# jetson_agx_m_2.net
KiCad netlist of a schematic drawn in Altium Designer
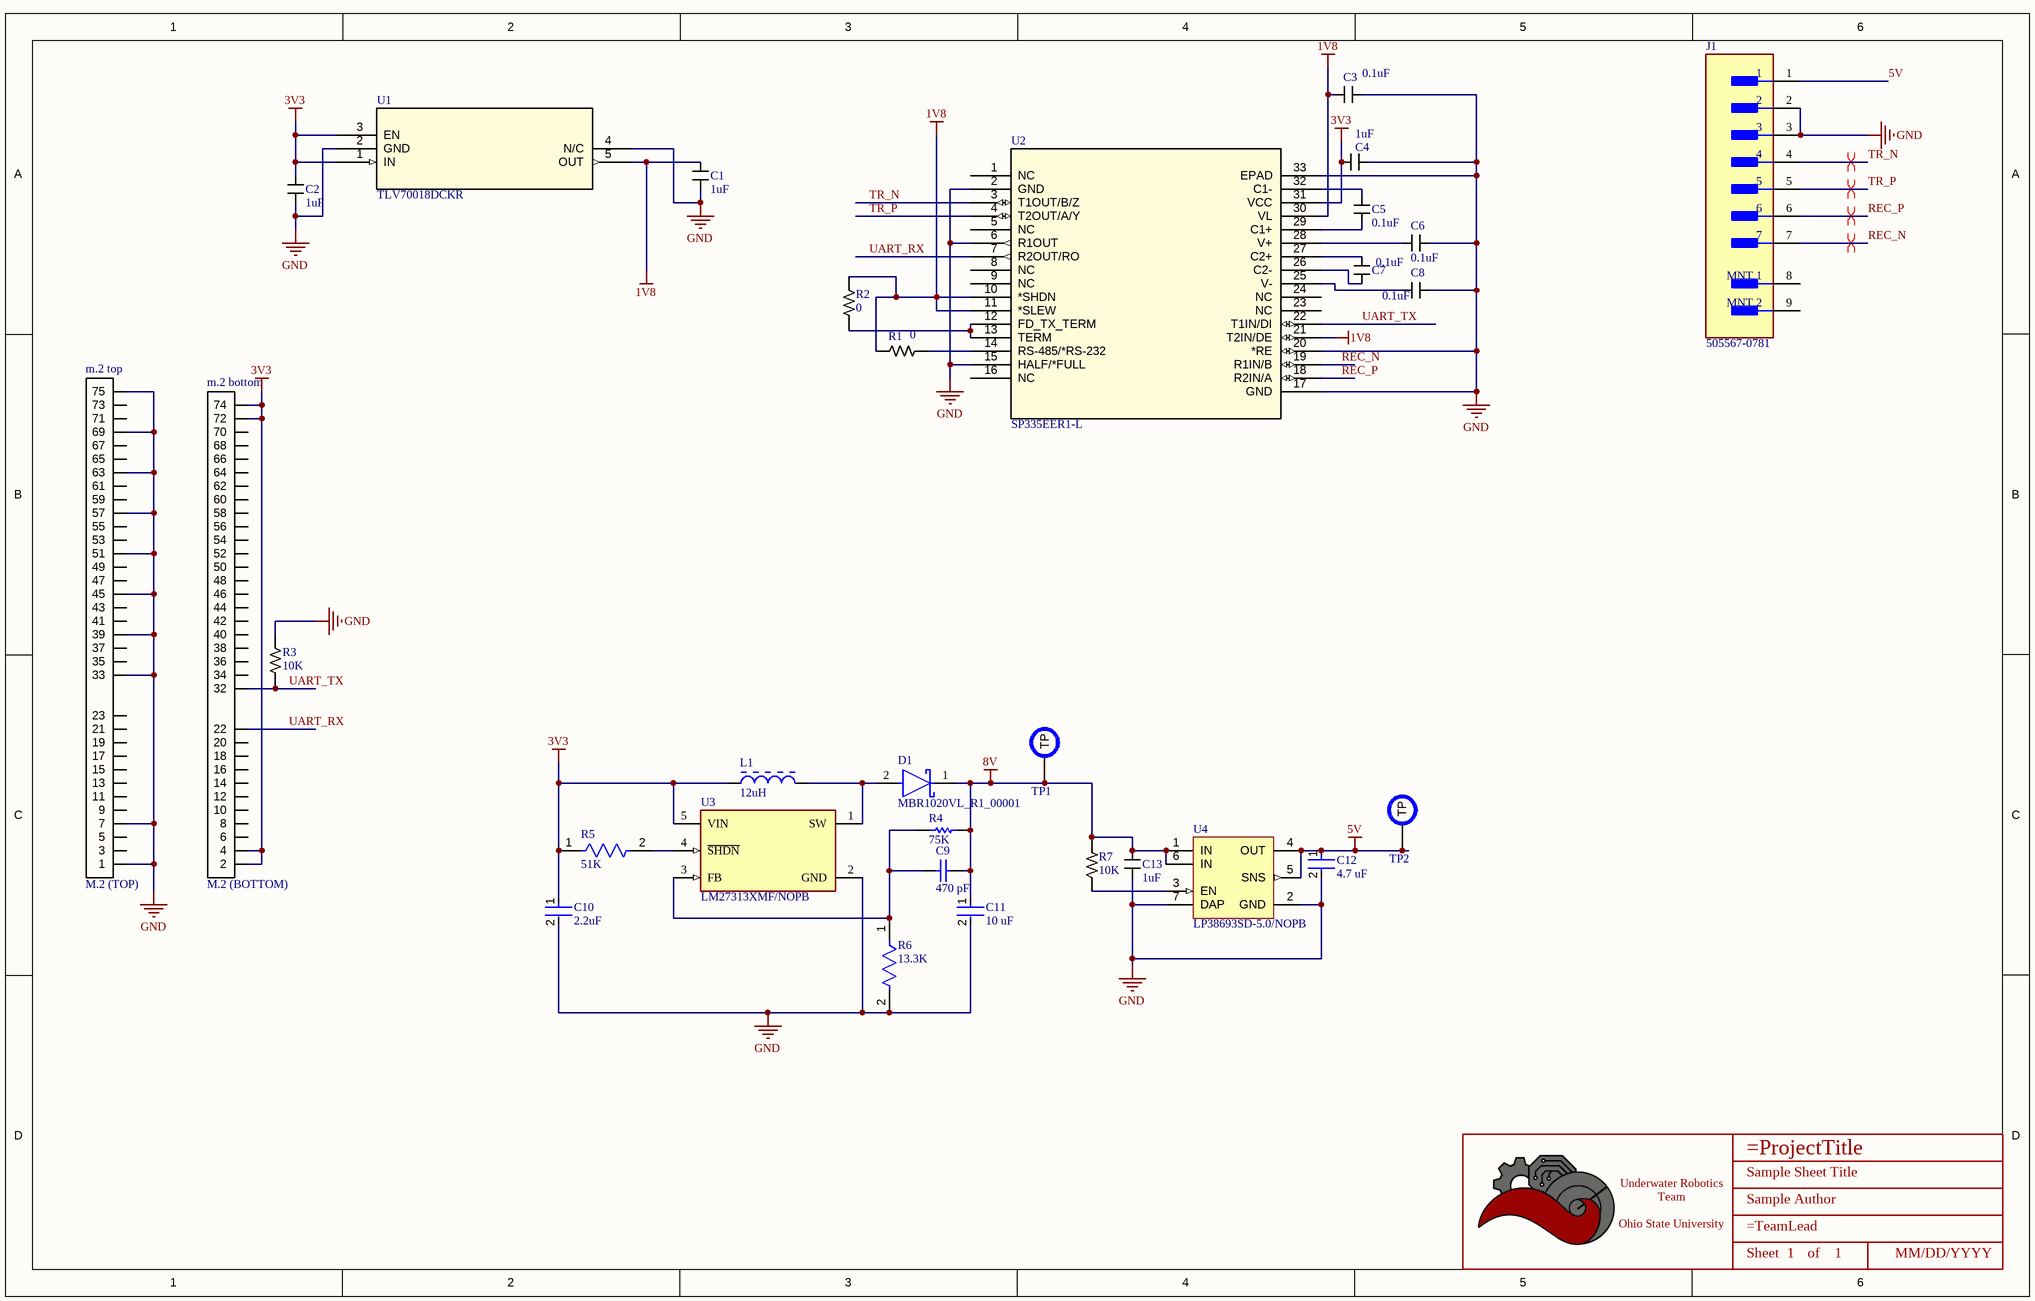
[diagram p0: jetson_agx_m.2.SchDoc]

(export (version "E")
  (design (tool "Eeschema 10.0.6"))
  (components
    (comp (ref "*")
      (value "Title_Block")
      (footprint "LOGO")
      (description "UWRT Schematic Title Block Template\r\n\r\nCreated June 2021, Dylan Trainor")
      (libsource (lib "UWRT") (part "Title_Block"))
    )
    (comp (ref "C1")
      (value "1uF")
      (footprint "CAPACITOR_0402")
      (description "Cap 1uF 16V +/-10%\r\nCeramic 0402")
      (fields
        (field (name "TOLERANCE") "+/- 10%")
        (field (name "VOLTAGE") "16V")
        (field (name "MADE BY") "Robert Pafford")
      )
      (libsource (lib "Capacitors") (part "CAPACITOR_1uF_0402"))
    )
    (comp (ref "C2")
      (value "1uF")
      (footprint "CAPACITOR_0402")
      (description "Cap 1uF 16V +/-10%\r\nCeramic 0402")
      (fields
        (field (name "TOLERANCE") "+/- 10%")
        (field (name "VOLTAGE") "16V")
        (field (name "MADE BY") "Robert Pafford")
      )
      (libsource (lib "Capacitors") (part "CAPACITOR_1uF_0402"))
    )
    (comp (ref "C3")
      (value "0.1uF")
      (footprint "CAPACITOR_0402")
      (description "Cap 100nF 25V +/-10%\r\nCeramic 0402")
      (fields
        (field (name "TOLERANCE") "+/- 10%")
        (field (name "VOLTAGE") "25V")
        (field (name "MADE BY") "Robert Pafford")
      )
      (libsource (lib "Capacitors") (part "CAPACITOR_0.1uF_0402"))
    )
    (comp (ref "C4")
      (value "1uF")
      (footprint "CAPACITOR_0402")
      (description "Cap 1uF 16V +/-10%\r\nCeramic 0402")
      (fields
        (field (name "TOLERANCE") "+/- 10%")
        (field (name "VOLTAGE") "16V")
        (field (name "MADE BY") "Robert Pafford")
      )
      (libsource (lib "Capacitors") (part "CAPACITOR_1uF_0402"))
    )
    (comp (ref "C5")
      (value "0.1uF")
      (footprint "CAPACITOR_0402")
      (description "Cap 100nF 25V +/-10%\r\nCeramic 0402")
      (fields
        (field (name "TOLERANCE") "+/- 10%")
        (field (name "VOLTAGE") "25V")
        (field (name "MADE BY") "Robert Pafford")
      )
      (libsource (lib "Capacitors") (part "CAPACITOR_0.1uF_0402"))
    )
    (comp (ref "C6")
      (value "0.1uF")
      (footprint "CAPACITOR_0402")
      (description "Cap 100nF 25V +/-10%\r\nCeramic 0402")
      (fields
        (field (name "TOLERANCE") "+/- 10%")
        (field (name "VOLTAGE") "25V")
        (field (name "MADE BY") "Robert Pafford")
      )
      (libsource (lib "Capacitors") (part "CAPACITOR_0.1uF_0402"))
    )
    (comp (ref "C7")
      (value "0.1uF")
      (footprint "CAPACITOR_0402")
      (description "Cap 100nF 25V +/-10%\r\nCeramic 0402")
      (fields
        (field (name "TOLERANCE") "+/- 10%")
        (field (name "VOLTAGE") "25V")
        (field (name "MADE BY") "Robert Pafford")
      )
      (libsource (lib "Capacitors") (part "CAPACITOR_0.1uF_0402"))
    )
    (comp (ref "C8")
      (value "0.1uF")
      (footprint "CAPACITOR_0402")
      (description "Cap 100nF 25V +/-10%\r\nCeramic 0402")
      (fields
        (field (name "TOLERANCE") "+/- 10%")
        (field (name "VOLTAGE") "25V")
        (field (name "MADE BY") "Robert Pafford")
      )
      (libsource (lib "Capacitors") (part "CAPACITOR_0.1uF_0402"))
    )
    (comp (ref "C9")
      (value "470 pF")
      (footprint "CAPC1005X55X25LL05T05")
      (fields (field (name "PART NUMBER") "VJ0402Y471KXQCW1BC") (field (name "MANUFACTURER") "Vitramon"))
      (libsource (lib "Altium Content Vault") (part "CAP"))
    )
    (comp (ref "C10")
      (value "2.2uF")
      (footprint "FP-GRT155-0_2-IPC_C")
      (description "Multi-Layer Ceramic Capacitor 2.2uF 10V X6S ±10% 0402 Paper T/R")
      (fields (field (name "TOLERANCE") "10%"))
      (libsource (lib "Altium Content Vault") (part "02cd4be3c70576c341d710602a673aa"))
    )
    (comp (ref "C11")
      (value "10 uF")
      (footprint "FP-CL07-IPC_C")
      (description "Cap Ceramic 10uF 10V X5R ±20% SMD 0402 +85°C Paper T/R")
      (fields (field (name "TOLERANCE") "20%"))
      (libsource (lib "Altium Content Vault") (part "b4654b650e69147ec39a6b967a45e02"))
    )
    (comp (ref "C12")
      (value "4.7 uF")
      (footprint "FP-CL282-IPC_C")
      (description "Cap Ceramic 4.7uF 10V X5R ±20% SMD 0402 +85°C Paper T/R")
      (fields (field (name "TOLERANCE") "20%"))
      (libsource (lib "Altium Content Vault") (part "b4654b650e69147ec39a6b967a45e02"))
    )
    (comp (ref "C13")
      (value "1uF")
      (footprint "CAPACITOR_0402")
      (description "Cap 1uF 16V +/-10%\r\nCeramic 0402")
      (fields
        (field (name "TOLERANCE") "+/- 10%")
        (field (name "VOLTAGE") "16V")
        (field (name "MADE BY") "Robert Pafford")
      )
      (libsource (lib "Capacitors") (part "CAPACITOR_1uF_0402"))
    )
    (comp (ref "D1")
      (value "MBR1020VL_R1_00001")
      (footprint "FP-MBR1020VL_R1_00001-MFG")
      (description "DIODE SCHOTTKY 20V 1A SOD123FL")
      (libsource (lib "Altium Content Vault") (part "c1678fac7984e62e0809fbf79c06691"))
    )
    (comp (ref "J1")
      (value "505567-0781")
      (footprint "FP-505567-0781-MFG")
      (libsource (lib "Altium Content Vault") (part "b0abd15a4b949e48c0a2e6945bb7dcd"))
    )
    (comp (ref "L1")
      (value "12uH")
      (footprint "BOUR-SDR0403-2_V")
      (fields (field (name "PARTNUMBER") "SDR0403-120ML") (field (name "MANUFACTURER") "Bourns"))
      (libsource (lib "Altium Content Vault") (part "BOUR-IND-2A"))
    )
    (comp (ref "m.2 bottom")
      (value "M.2 (BOTTOM)")
      (footprint "M.2 (bottom)")
      (fields (field (name "CREATED BY") "Ethan Rosati") (field (name "REVIEWED BY") "*"))
      (libsource (lib "Connectors") (part "M.2 (BOTTOM)"))
    )
    (comp (ref "m.2 top")
      (value "M.2 (TOP)")
      (footprint "M.2 (top)")
      (description "M.2 E-Key top fingers")
      (fields (field (name "CREATED BY") "Ethan Rosati") (field (name "REVIEWED BY") "*"))
      (libsource (lib "Connectors") (part "M.2 (TOP)"))
    )
    (comp (ref "R1")
      (value "0 Ohm 1% 1/16W")
      (footprint "RESISTOR_0402")
      (description "RES 0 OHM 1% 1/16W 0402")
      (fields
        (field (name "TOLERANCE") "+/- 1%")
        (field (name "VALUE  (OHMS)") "0")
        (field (name "MADE BY") "Robert Pafford")
      )
      (libsource (lib "Resistors") (part "RESISTOR_0_0402"))
    )
    (comp (ref "R2")
      (value "0 Ohm 1% 1/16W")
      (footprint "RESISTOR_0402")
      (description "RES 0 OHM 1% 1/16W 0402")
      (fields
        (field (name "TOLERANCE") "+/- 1%")
        (field (name "VALUE  (OHMS)") "0")
        (field (name "MADE BY") "Robert Pafford")
      )
      (libsource (lib "Resistors") (part "RESISTOR_0_0402"))
    )
    (comp (ref "R3")
      (value "10k Ohm 1% 1/16W")
      (footprint "RESISTOR_0402")
      (description "RES 10k OHM 1% 1/16W 0402")
      (fields
        (field (name "TOLERANCE") "+/- 1%")
        (field (name "VALUE  (OHMS)") "10K")
        (field (name "MADE BY") "Robert Pafford")
      )
      (libsource (lib "Resistors") (part "RESISTOR_10K_0402"))
    )
    (comp (ref "R4")
      (value "75K")
      (footprint "RESC1005X40X25NL10T10")
      (fields (field (name "PART NUMBER") "ERA-2AEB753X") (field (name "MANUFACTURER") "Panasonic"))
      (libsource (lib "Altium Content Vault") (part "RES"))
    )
    (comp (ref "R5")
      (value "51K")
      (footprint "FP-RMCF0402-MFG")
      (description "51kΩ ±5% 0.063W 0402 Thick Film Chip Resistor AEC-Q200 compliant")
      (fields (field (name "TOLERANCE") "5%"))
      (libsource (lib "Altium Content Vault") (part "1029c3af85768c4190bb7ad29bc67b5"))
    )
    (comp (ref "R6")
      (value "13.3K")
      (footprint "FP-CR0402-MFG")
      (description "Thick Film Chip Resistors 0402 13.3kΩ 0.0625W 1% 100ppm/°C")
      (fields (field (name "TOLERANCE") "1%"))
      (libsource (lib "Altium Content Vault") (part "1029c3af85768c4190bb7ad29bc67b5"))
    )
    (comp (ref "R7")
      (value "10k Ohm 1% 1/16W")
      (footprint "RESISTOR_0402")
      (description "RES 10k OHM 1% 1/16W 0402")
      (fields
        (field (name "TOLERANCE") "+/- 1%")
        (field (name "VALUE  (OHMS)") "10K")
        (field (name "MADE BY") "Robert Pafford")
      )
      (libsource (lib "Resistors") (part "RESISTOR_10K_0402"))
    )
    (comp (ref "TP1")
      (value "PCB Test Point")
      (footprint "TESTPOINT_1.2MM")
      (fields (field (name "MADE BY") "Robert Pafford"))
      (libsource (lib "Connectors") (part "TESTPOINT"))
    )
    (comp (ref "TP2")
      (value "PCB Test Point")
      (footprint "TESTPOINT_1.2MM")
      (fields (field (name "MADE BY") "Robert Pafford"))
      (libsource (lib "Connectors") (part "TESTPOINT"))
    )
    (comp (ref "U1")
      (value "TLV70018DCKR")
      (footprint "SOT-353")
      (description "Fixed Positive LDO Regulator, 1.8V, PMOS, PDSO5")
      (fields (field (name "MADE BY") "Ethan Rosati") (field (name "REVIEWED BY") "*"))
      (libsource (lib "Integrated Circuits") (part "TLV70018DCKR"))
    )
    (comp (ref "U2")
      (value "SP335EER1-L")
      (footprint "QFN-32")
      (description "1/1, 2/2 Transceiver Full RS232, RS422, RS485 32-QFN (5x5)")
      (fields (field (name "CREATED BY") "Ethan Rosati") (field (name "REVIEWED BY") "*"))
      (libsource (lib "Integrated Circuits") (part "SP335EER1-L"))
    )
    (comp (ref "U3")
      (value "LM27313XMF/NOPB")
      (footprint "FP-DBV0005A-IPC_A")
      (description "IC REG BOOST ADJ 800MA SOT23-5")
      (libsource (lib "Altium Content Vault") (part "169f9435efc31d3fe74d235977c1b19"))
    )
    (comp (ref "U4")
      (value "LP38693SD-5.0/NOPB")
      (footprint "NGG0006A_V")
      (fields (field (name "MANUFACTURER") "Texas Instruments"))
      (libsource (lib "Altium Content Vault") (part "PM-REG-LP38692-IL7"))
    )
  )
  (nets
    (net (code "1") (name "/REC_N") (class "Default")
      (node (ref "J1") (pin "7") (pinfunction "7_7") (pintype "passive"))
      (node (ref "U2") (pin "19") (pinfunction "R1IN/B_19") (pintype "bidirectional"))
    )
    (net (code "2") (name "/REC_P") (class "Default")
      (node (ref "J1") (pin "6") (pinfunction "6_6") (pintype "passive"))
      (node (ref "U2") (pin "18") (pinfunction "R2IN/A_18") (pintype "bidirectional"))
    )
    (net (code "3") (name "/TR_N") (class "Default")
      (node (ref "J1") (pin "4") (pinfunction "4_4") (pintype "passive"))
      (node (ref "U2") (pin "3") (pinfunction "T1OUT/B/Z_3") (pintype "bidirectional"))
    )
    (net (code "4") (name "/TR_P") (class "Default")
      (node (ref "J1") (pin "5") (pinfunction "5_5") (pintype "passive"))
      (node (ref "U2") (pin "4") (pinfunction "T2OUT/A/Y_4") (pintype "bidirectional"))
    )
    (net (code "5") (name "/UART_RX") (class "Default")
      (node (ref "U2") (pin "7") (pinfunction "R2OUT/RO_7") (pintype "output"))
      (node (ref "m.2 bottom") (pin "22") (pinfunction "22_22") (pintype "passive"))
    )
    (net (code "6") (name "/UART_TX") (class "Default")
      (node (ref "R3") (pin "1") (pinfunction "1_1") (pintype "passive"))
      (node (ref "U2") (pin "22") (pinfunction "T1IN/DI_22") (pintype "bidirectional"))
      (node (ref "m.2 bottom") (pin "32") (pinfunction "32_32") (pintype "passive"))
    )
    (net (code "7") (name "1V8") (class "Default")
      (node (ref "C1") (pin "1") (pinfunction "1_1") (pintype "passive"))
      (node (ref "C3") (pin "1") (pinfunction "1_1") (pintype "passive"))
      (node (ref "R1") (pin "2") (pinfunction "2_2") (pintype "passive"))
      (node (ref "R2") (pin "2") (pinfunction "2_2") (pintype "passive"))
      (node (ref "U1") (pin "5") (pinfunction "OUT_5") (pintype "output"))
      (node (ref "U2") (pin "10") (pinfunction "*SHDN_10") (pintype "passive"))
      (node (ref "U2") (pin "11") (pinfunction "*SLEW_11") (pintype "passive"))
      (node (ref "U2") (pin "21") (pinfunction "T2IN/DE_21") (pintype "bidirectional"))
      (node (ref "U2") (pin "30") (pinfunction "VL_30") (pintype "power_in"))
    )
    (net (code "8") (name "3V3") (class "Default")
      (node (ref "C10") (pin "1") (pinfunction "1_1") (pintype "passive"))
      (node (ref "C2") (pin "1") (pinfunction "1_1") (pintype "passive"))
      (node (ref "C4") (pin "1") (pinfunction "1_1") (pintype "passive"))
      (node (ref "L1") (pin "1") (pinfunction "1_1") (pintype "passive"))
      (node (ref "R5") (pin "1") (pinfunction "1_1") (pintype "passive"))
      (node (ref "U1") (pin "1") (pinfunction "IN_1") (pintype "input"))
      (node (ref "U1") (pin "3") (pinfunction "EN_3") (pintype "passive"))
      (node (ref "U2") (pin "31") (pinfunction "VCC_31") (pintype "power_in"))
      (node (ref "U3") (pin "5") (pinfunction "VIN_5") (pintype "power_in"))
      (node (ref "m.2 bottom") (pin "2") (pinfunction "2_2") (pintype "passive"))
      (node (ref "m.2 bottom") (pin "4") (pinfunction "4_4") (pintype "passive"))
      (node (ref "m.2 bottom") (pin "72") (pinfunction "72_72") (pintype "passive"))
      (node (ref "m.2 bottom") (pin "74") (pinfunction "74_74") (pintype "passive"))
    )
    (net (code "9") (name "5V") (class "Default")
      (node (ref "C12") (pin "1") (pinfunction "1_1") (pintype "passive"))
      (node (ref "J1") (pin "1") (pinfunction "1_1") (pintype "passive"))
      (node (ref "TP2") (pin "TP") (pinfunction "TP_TP") (pintype "passive"))
      (node (ref "U4") (pin "4") (pinfunction "OUT_4") (pintype "power_in"))
      (node (ref "U4") (pin "5") (pinfunction "SNS_5") (pintype "output"))
    )
    (net (code "10") (name "8V") (class "Default")
      (node (ref "C11") (pin "1") (pinfunction "1_1") (pintype "passive"))
      (node (ref "C13") (pin "1") (pinfunction "1_1") (pintype "passive"))
      (node (ref "C9") (pin "2") (pinfunction "2_2") (pintype "passive"))
      (node (ref "D1") (pin "1") (pinfunction "C_1") (pintype "passive"))
      (node (ref "R4") (pin "2") (pinfunction "2_2") (pintype "passive"))
      (node (ref "R7") (pin "1") (pinfunction "1_1") (pintype "passive"))
      (node (ref "TP1") (pin "TP") (pinfunction "TP_TP") (pintype "passive"))
      (node (ref "U4") (pin "1") (pinfunction "IN_1") (pintype "power_in"))
      (node (ref "U4") (pin "6") (pinfunction "IN_6") (pintype "power_in"))
    )
    (net (code "11") (name "GND") (class "Default")
      (node (ref "C1") (pin "2") (pinfunction "2_2") (pintype "passive"))
      (node (ref "C10") (pin "2") (pinfunction "2_2") (pintype "passive"))
      (node (ref "C11") (pin "2") (pinfunction "2_2") (pintype "passive"))
      (node (ref "C12") (pin "2") (pinfunction "2_2") (pintype "passive"))
      (node (ref "C13") (pin "2") (pinfunction "2_2") (pintype "passive"))
      (node (ref "C2") (pin "2") (pinfunction "2_2") (pintype "passive"))
      (node (ref "C3") (pin "2") (pinfunction "2_2") (pintype "passive"))
      (node (ref "C4") (pin "2") (pinfunction "2_2") (pintype "passive"))
      (node (ref "C6") (pin "2") (pinfunction "2_2") (pintype "passive"))
      (node (ref "C8") (pin "2") (pinfunction "2_2") (pintype "passive"))
      (node (ref "J1") (pin "2") (pinfunction "2_2") (pintype "passive"))
      (node (ref "J1") (pin "3") (pinfunction "3_3") (pintype "passive"))
      (node (ref "R3") (pin "2") (pinfunction "2_2") (pintype "passive"))
      (node (ref "R6") (pin "2") (pinfunction "2_2") (pintype "passive"))
      (node (ref "U1") (pin "2") (pinfunction "GND_2") (pintype "passive"))
      (node (ref "U1") (pin "4") (pinfunction "N/C_4") (pintype "power_in"))
      (node (ref "U2") (pin "15") (pinfunction "HALF/*FULL_15") (pintype "passive"))
      (node (ref "U2") (pin "17") (pinfunction "GND_17") (pintype "power_in"))
      (node (ref "U2") (pin "2") (pinfunction "GND_2") (pintype "power_in"))
      (node (ref "U2") (pin "20") (pinfunction "*RE_20") (pintype "bidirectional"))
      (node (ref "U2") (pin "33") (pinfunction "EPAD_33") (pintype "passive"))
      (node (ref "U2") (pin "6") (pinfunction "R1OUT_6") (pintype "output"))
      (node (ref "U3") (pin "2") (pinfunction "GND_2") (pintype "power_in"))
      (node (ref "U4") (pin "2") (pinfunction "GND_2") (pintype "power_in"))
      (node (ref "U4") (pin "7") (pinfunction "DAP_7") (pintype "power_in"))
      (node (ref "m.2 top") (pin "1") (pinfunction "1_1") (pintype "passive"))
      (node (ref "m.2 top") (pin "33") (pinfunction "33_33") (pintype "passive"))
      (node (ref "m.2 top") (pin "39") (pinfunction "39_39") (pintype "passive"))
      (node (ref "m.2 top") (pin "45") (pinfunction "45_45") (pintype "passive"))
      (node (ref "m.2 top") (pin "51") (pinfunction "51_51") (pintype "passive"))
      (node (ref "m.2 top") (pin "57") (pinfunction "57_57") (pintype "passive"))
      (node (ref "m.2 top") (pin "63") (pinfunction "63_63") (pintype "passive"))
      (node (ref "m.2 top") (pin "69") (pinfunction "69_69") (pintype "passive"))
      (node (ref "m.2 top") (pin "7") (pinfunction "7_7") (pintype "passive"))
      (node (ref "m.2 top") (pin "75") (pinfunction "75_75") (pintype "passive"))
    )
    (net (code "12") (name "Net-(D1-A)") (class "Default")
      (node (ref "D1") (pin "2") (pinfunction "A_2") (pintype "passive"))
      (node (ref "L1") (pin "2") (pinfunction "2_2") (pintype "passive"))
      (node (ref "U3") (pin "1") (pinfunction "SW_1") (pintype "power_in"))
    )
    (net (code "13") (name "Net-(U2-C1+)") (class "Default")
      (node (ref "C5") (pin "2") (pinfunction "2_2") (pintype "passive"))
      (node (ref "U2") (pin "29") (pinfunction "C1+_29") (pintype "passive"))
    )
    (net (code "14") (name "Net-(U2-C1-)") (class "Default")
      (node (ref "C5") (pin "1") (pinfunction "1_1") (pintype "passive"))
      (node (ref "U2") (pin "32") (pinfunction "C1-_32") (pintype "passive"))
    )
    (net (code "15") (name "Net-(U2-C2+)") (class "Default")
      (node (ref "C7") (pin "1") (pinfunction "1_1") (pintype "passive"))
      (node (ref "U2") (pin "27") (pinfunction "C2+_27") (pintype "passive"))
    )
    (net (code "16") (name "Net-(U2-C2-)") (class "Default")
      (node (ref "C7") (pin "2") (pinfunction "2_2") (pintype "passive"))
      (node (ref "U2") (pin "26") (pinfunction "C2-_26") (pintype "passive"))
    )
    (net (code "17") (name "Net-(U2-FD_TX_TERM)") (class "Default")
      (node (ref "R2") (pin "1") (pinfunction "1_1") (pintype "passive"))
      (node (ref "U2") (pin "12") (pinfunction "FD_TX_TERM_12") (pintype "passive"))
      (node (ref "U2") (pin "13") (pinfunction "TERM_13") (pintype "passive"))
    )
    (net (code "18") (name "Net-(U2-RS-485{slash}*RS-232)") (class "Default")
      (node (ref "R1") (pin "1") (pinfunction "1_1") (pintype "passive"))
      (node (ref "U2") (pin "14") (pinfunction "RS-485/*RS-232_14") (pintype "passive"))
    )
    (net (code "19") (name "Net-(U2-V+)") (class "Default")
      (node (ref "C6") (pin "1") (pinfunction "1_1") (pintype "passive"))
      (node (ref "U2") (pin "28") (pinfunction "V+_28") (pintype "power_in"))
    )
    (net (code "20") (name "Net-(U2-V-)") (class "Default")
      (node (ref "C8") (pin "1") (pinfunction "1_1") (pintype "passive"))
      (node (ref "U2") (pin "25") (pinfunction "V-_25") (pintype "power_in"))
    )
    (net (code "21") (name "Net-(U3-FB)") (class "Default")
      (node (ref "C9") (pin "1") (pinfunction "1_1") (pintype "passive"))
      (node (ref "R4") (pin "1") (pinfunction "1_1") (pintype "passive"))
      (node (ref "R6") (pin "1") (pinfunction "1_1") (pintype "passive"))
      (node (ref "U3") (pin "3") (pinfunction "FB_3") (pintype "input"))
    )
    (net (code "22") (name "Net-(U3-~{SHDN})") (class "Default")
      (node (ref "R5") (pin "2") (pinfunction "2_2") (pintype "passive"))
      (node (ref "U3") (pin "4") (pinfunction "~{SHDN}_4") (pintype "input"))
    )
    (net (code "23") (name "Net-(U4-EN)") (class "Default")
      (node (ref "R7") (pin "2") (pinfunction "2_2") (pintype "passive"))
      (node (ref "U4") (pin "3") (pinfunction "EN_3") (pintype "input"))
    )
    (net (code "24") (name "unconnected-(J1-MNT_1-Pad8)") (class "Default")
      (node (ref "J1") (pin "8") (pinfunction "MNT_1_8") (pintype "passive"))
    )
    (net (code "25") (name "unconnected-(J1-MNT_2-Pad9)") (class "Default")
      (node (ref "J1") (pin "9") (pinfunction "MNT_2_9") (pintype "passive"))
    )
    (net (code "26") (name "unconnected-(U2-NC-Pad1)") (class "Default")
      (node (ref "U2") (pin "1") (pinfunction "NC_1") (pintype "passive"))
    )
    (net (code "27") (name "unconnected-(U2-NC-Pad5)") (class "Default")
      (node (ref "U2") (pin "5") (pinfunction "NC_5") (pintype "passive"))
    )
    (net (code "28") (name "unconnected-(U2-NC-Pad8)") (class "Default")
      (node (ref "U2") (pin "8") (pinfunction "NC_8") (pintype "passive"))
    )
    (net (code "29") (name "unconnected-(U2-NC-Pad9)") (class "Default")
      (node (ref "U2") (pin "9") (pinfunction "NC_9") (pintype "passive"))
    )
    (net (code "30") (name "unconnected-(U2-NC-Pad16)") (class "Default")
      (node (ref "U2") (pin "16") (pinfunction "NC_16") (pintype "passive"))
    )
    (net (code "31") (name "unconnected-(U2-NC-Pad23)") (class "Default")
      (node (ref "U2") (pin "23") (pinfunction "NC_23") (pintype "passive"))
    )
    (net (code "32") (name "unconnected-(U2-NC-Pad24)") (class "Default")
      (node (ref "U2") (pin "24") (pinfunction "NC_24") (pintype "passive"))
    )
    (net (code "33") (name "unconnected-(m.2 bottom-Pad6)") (class "Default")
      (node (ref "m.2 bottom") (pin "6") (pinfunction "6_6") (pintype "passive"))
    )
    (net (code "34") (name "unconnected-(m.2 bottom-Pad8)") (class "Default")
      (node (ref "m.2 bottom") (pin "8") (pinfunction "8_8") (pintype "passive"))
    )
    (net (code "35") (name "unconnected-(m.2 bottom-Pad10)") (class "Default")
      (node (ref "m.2 bottom") (pin "10") (pinfunction "10_10") (pintype "passive"))
    )
    (net (code "36") (name "unconnected-(m.2 bottom-Pad12)") (class "Default")
      (node (ref "m.2 bottom") (pin "12") (pinfunction "12_12") (pintype "passive"))
    )
    (net (code "37") (name "unconnected-(m.2 bottom-Pad14)") (class "Default")
      (node (ref "m.2 bottom") (pin "14") (pinfunction "14_14") (pintype "passive"))
    )
    (net (code "38") (name "unconnected-(m.2 bottom-Pad16)") (class "Default")
      (node (ref "m.2 bottom") (pin "16") (pinfunction "16_16") (pintype "passive"))
    )
    (net (code "39") (name "unconnected-(m.2 bottom-Pad18)") (class "Default")
      (node (ref "m.2 bottom") (pin "18") (pinfunction "18_18") (pintype "passive"))
    )
    (net (code "40") (name "unconnected-(m.2 bottom-Pad20)") (class "Default")
      (node (ref "m.2 bottom") (pin "20") (pinfunction "20_20") (pintype "passive"))
    )
    (net (code "41") (name "unconnected-(m.2 bottom-Pad34)") (class "Default")
      (node (ref "m.2 bottom") (pin "34") (pinfunction "34_34") (pintype "passive"))
    )
    (net (code "42") (name "unconnected-(m.2 bottom-Pad36)") (class "Default")
      (node (ref "m.2 bottom") (pin "36") (pinfunction "36_36") (pintype "passive"))
    )
    (net (code "43") (name "unconnected-(m.2 bottom-Pad38)") (class "Default")
      (node (ref "m.2 bottom") (pin "38") (pinfunction "38_38") (pintype "passive"))
    )
    (net (code "44") (name "unconnected-(m.2 bottom-Pad40)") (class "Default")
      (node (ref "m.2 bottom") (pin "40") (pinfunction "40_40") (pintype "passive"))
    )
    (net (code "45") (name "unconnected-(m.2 bottom-Pad42)") (class "Default")
      (node (ref "m.2 bottom") (pin "42") (pinfunction "42_42") (pintype "passive"))
    )
    (net (code "46") (name "unconnected-(m.2 bottom-Pad44)") (class "Default")
      (node (ref "m.2 bottom") (pin "44") (pinfunction "44_44") (pintype "passive"))
    )
    (net (code "47") (name "unconnected-(m.2 bottom-Pad46)") (class "Default")
      (node (ref "m.2 bottom") (pin "46") (pinfunction "46_46") (pintype "passive"))
    )
    (net (code "48") (name "unconnected-(m.2 bottom-Pad48)") (class "Default")
      (node (ref "m.2 bottom") (pin "48") (pinfunction "48_48") (pintype "passive"))
    )
    (net (code "49") (name "unconnected-(m.2 bottom-Pad50)") (class "Default")
      (node (ref "m.2 bottom") (pin "50") (pinfunction "50_50") (pintype "passive"))
    )
    (net (code "50") (name "unconnected-(m.2 bottom-Pad52)") (class "Default")
      (node (ref "m.2 bottom") (pin "52") (pinfunction "52_52") (pintype "passive"))
    )
    (net (code "51") (name "unconnected-(m.2 bottom-Pad54)") (class "Default")
      (node (ref "m.2 bottom") (pin "54") (pinfunction "54_54") (pintype "passive"))
    )
    (net (code "52") (name "unconnected-(m.2 bottom-Pad56)") (class "Default")
      (node (ref "m.2 bottom") (pin "56") (pinfunction "56_56") (pintype "passive"))
    )
    (net (code "53") (name "unconnected-(m.2 bottom-Pad58)") (class "Default")
      (node (ref "m.2 bottom") (pin "58") (pinfunction "58_58") (pintype "passive"))
    )
    (net (code "54") (name "unconnected-(m.2 bottom-Pad60)") (class "Default")
      (node (ref "m.2 bottom") (pin "60") (pinfunction "60_60") (pintype "passive"))
    )
    (net (code "55") (name "unconnected-(m.2 bottom-Pad62)") (class "Default")
      (node (ref "m.2 bottom") (pin "62") (pinfunction "62_62") (pintype "passive"))
    )
    (net (code "56") (name "unconnected-(m.2 bottom-Pad64)") (class "Default")
      (node (ref "m.2 bottom") (pin "64") (pinfunction "64_64") (pintype "passive"))
    )
    (net (code "57") (name "unconnected-(m.2 bottom-Pad66)") (class "Default")
      (node (ref "m.2 bottom") (pin "66") (pinfunction "66_66") (pintype "passive"))
    )
    (net (code "58") (name "unconnected-(m.2 bottom-Pad68)") (class "Default")
      (node (ref "m.2 bottom") (pin "68") (pinfunction "68_68") (pintype "passive"))
    )
    (net (code "59") (name "unconnected-(m.2 bottom-Pad70)") (class "Default")
      (node (ref "m.2 bottom") (pin "70") (pinfunction "70_70") (pintype "passive"))
    )
    (net (code "60") (name "unconnected-(m.2 top-Pad3)") (class "Default")
      (node (ref "m.2 top") (pin "3") (pinfunction "3_3") (pintype "passive"))
    )
    (net (code "61") (name "unconnected-(m.2 top-Pad5)") (class "Default")
      (node (ref "m.2 top") (pin "5") (pinfunction "5_5") (pintype "passive"))
    )
    (net (code "62") (name "unconnected-(m.2 top-Pad9)") (class "Default")
      (node (ref "m.2 top") (pin "9") (pinfunction "9_9") (pintype "passive"))
    )
    (net (code "63") (name "unconnected-(m.2 top-Pad11)") (class "Default")
      (node (ref "m.2 top") (pin "11") (pinfunction "11_11") (pintype "passive"))
    )
    (net (code "64") (name "unconnected-(m.2 top-Pad13)") (class "Default")
      (node (ref "m.2 top") (pin "13") (pinfunction "13_13") (pintype "passive"))
    )
    (net (code "65") (name "unconnected-(m.2 top-Pad15)") (class "Default")
      (node (ref "m.2 top") (pin "15") (pinfunction "15_15") (pintype "passive"))
    )
    (net (code "66") (name "unconnected-(m.2 top-Pad17)") (class "Default")
      (node (ref "m.2 top") (pin "17") (pinfunction "17_17") (pintype "passive"))
    )
    (net (code "67") (name "unconnected-(m.2 top-Pad19)") (class "Default")
      (node (ref "m.2 top") (pin "19") (pinfunction "19_19") (pintype "passive"))
    )
    (net (code "68") (name "unconnected-(m.2 top-Pad21)") (class "Default")
      (node (ref "m.2 top") (pin "21") (pinfunction "21_21") (pintype "passive"))
    )
    (net (code "69") (name "unconnected-(m.2 top-Pad23)") (class "Default")
      (node (ref "m.2 top") (pin "23") (pinfunction "23_23") (pintype "passive"))
    )
    (net (code "70") (name "unconnected-(m.2 top-Pad35)") (class "Default")
      (node (ref "m.2 top") (pin "35") (pinfunction "35_35") (pintype "passive"))
    )
    (net (code "71") (name "unconnected-(m.2 top-Pad37)") (class "Default")
      (node (ref "m.2 top") (pin "37") (pinfunction "37_37") (pintype "passive"))
    )
    (net (code "72") (name "unconnected-(m.2 top-Pad41)") (class "Default")
      (node (ref "m.2 top") (pin "41") (pinfunction "41_41") (pintype "passive"))
    )
    (net (code "73") (name "unconnected-(m.2 top-Pad43)") (class "Default")
      (node (ref "m.2 top") (pin "43") (pinfunction "43_43") (pintype "passive"))
    )
    (net (code "74") (name "unconnected-(m.2 top-Pad47)") (class "Default")
      (node (ref "m.2 top") (pin "47") (pinfunction "47_47") (pintype "passive"))
    )
    (net (code "75") (name "unconnected-(m.2 top-Pad49)") (class "Default")
      (node (ref "m.2 top") (pin "49") (pinfunction "49_49") (pintype "passive"))
    )
    (net (code "76") (name "unconnected-(m.2 top-Pad53)") (class "Default")
      (node (ref "m.2 top") (pin "53") (pinfunction "53_53") (pintype "passive"))
    )
    (net (code "77") (name "unconnected-(m.2 top-Pad55)") (class "Default")
      (node (ref "m.2 top") (pin "55") (pinfunction "55_55") (pintype "passive"))
    )
    (net (code "78") (name "unconnected-(m.2 top-Pad59)") (class "Default")
      (node (ref "m.2 top") (pin "59") (pinfunction "59_59") (pintype "passive"))
    )
    (net (code "79") (name "unconnected-(m.2 top-Pad61)") (class "Default")
      (node (ref "m.2 top") (pin "61") (pinfunction "61_61") (pintype "passive"))
    )
    (net (code "80") (name "unconnected-(m.2 top-Pad65)") (class "Default")
      (node (ref "m.2 top") (pin "65") (pinfunction "65_65") (pintype "passive"))
    )
    (net (code "81") (name "unconnected-(m.2 top-Pad67)") (class "Default")
      (node (ref "m.2 top") (pin "67") (pinfunction "67_67") (pintype "passive"))
    )
    (net (code "82") (name "unconnected-(m.2 top-Pad71)") (class "Default")
      (node (ref "m.2 top") (pin "71") (pinfunction "71_71") (pintype "passive"))
    )
    (net (code "83") (name "unconnected-(m.2 top-Pad73)") (class "Default")
      (node (ref "m.2 top") (pin "73") (pinfunction "73_73") (pintype "passive"))
    )
  )
)
